# LightSensor1.net
KiCad netlist of a schematic drawn in EAGLE
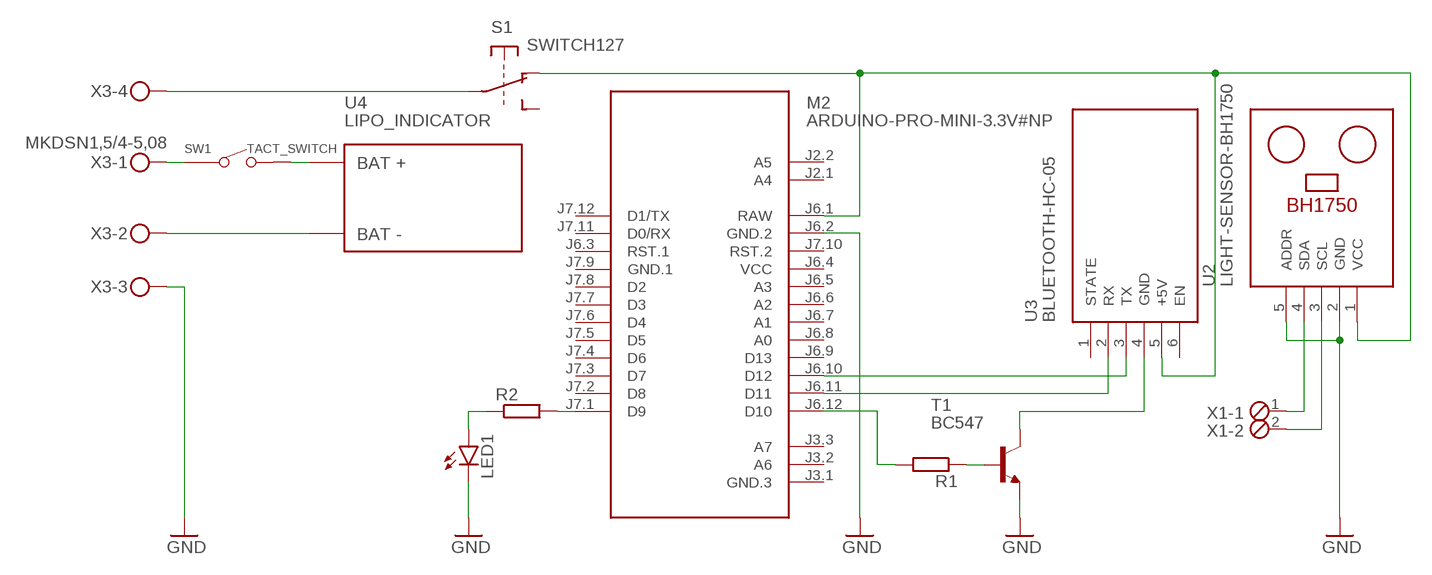
[diagram p0: schematic, sheet 1]

(export (version "E")
  (design (tool "Eeschema 10.0.6"))
  (components
    (comp (ref "LED1")
      (value "LED3MM")
      (footprint "eagle-import:LED3MM")
      (libsource (lib "eagle-import") (part "LED3MM"))
    )
    (comp (ref "M2")
      (value "ARDUINO-PRO-MINI-3.3V#NP")
      (footprint "eagle-import:ARDUINO-PRO-MINI#NP")
      (libsource (lib "eagle-import") (part "ARDUINO-PRO-MINI-#NP3.3V"))
    )
    (comp (ref "R1")
      (value "R-EU_0207/10")
      (footprint "eagle-import:0207_10")
      (libsource (lib "eagle-import") (part "R-EU_0207/10"))
    )
    (comp (ref "R2")
      (value "R-EU_0207/10")
      (footprint "eagle-import:0207_10")
      (libsource (lib "eagle-import") (part "R-EU_0207/10"))
    )
    (comp (ref "S1")
      (value "SWITCH127")
      (footprint "eagle-import:SWITCH127")
      (libsource (lib "eagle-import") (part "SWITCH127"))
    )
    (comp (ref "SW1")
      (value "TACT_SWITCH")
      (footprint "eagle-import:SW2-5.0-6.0X3.0X4.3MM")
      (libsource (lib "eagle-import") (part "TACT_SWITCH"))
    )
    (comp (ref "T1")
      (value "BC547")
      (footprint "eagle-import:TO92")
      (libsource (lib "eagle-import") (part "BC547"))
    )
    (comp (ref "U2")
      (value "LIGHT-SENSOR-BH1750")
      (footprint "eagle-import:LIGHT-SENSOR-BH1750")
      (libsource (lib "eagle-import") (part "LIGHT-SENSOR-BH1750"))
    )
    (comp (ref "U3")
      (value "BLUETOOTH-HC-05")
      (footprint "eagle-import:WIRELESS-BLUETOOTH-HC-05")
      (libsource (lib "eagle-import") (part "WIRELESS-BLUETOOTH-HC-05"))
    )
    (comp (ref "U4")
      (value "LIPO_INDICATOR")
      (footprint "eagle-import:INDICATROR_NR1")
      (libsource (lib "eagle-import") (part "LIPO_INDICATOR"))
    )
    (comp (ref "X1")
      (value "MPT2")
      (footprint "eagle-import:2POL254")
      (libsource (lib "eagle-import") (part "MPT2"))
    )
    (comp (ref "X3")
      (value "MKDSN1,5/4-5,08")
      (footprint "eagle-import:MKDSN1,5_4-5,08")
      (libsource (lib "eagle-import") (part "MKDSN1,5/4-5,08"))
    )
  )
  (nets
    (net (code "1") (name "/GND.1") (class "Default")
      (node (ref "M2") (pin "J7.9") (pinfunction "GND.1_J7.9") (pintype "power_in"))
    )
    (net (code "2") (name "/VCC") (class "Default")
      (node (ref "M2") (pin "J6.4") (pinfunction "VCC_J6.4") (pintype "power_in"))
    )
    (net (code "3") (name "GND") (class "Default")
      (node (ref "LED1") (pin "K") (pinfunction "C_K") (pintype "passive"))
      (node (ref "M2") (pin "J6.2") (pinfunction "GND.2_J6.2") (pintype "power_in"))
      (node (ref "T1") (pin "1") (pinfunction "E_1") (pintype "passive"))
      (node (ref "U2") (pin "2") (pinfunction "GND_2") (pintype "power_in"))
      (node (ref "U2") (pin "5") (pinfunction "ADDR_5") (pintype "bidirectional"))
      (node (ref "X3") (pin "3") (pinfunction "KL_3") (pintype "passive"))
    )
    (net (code "4") (name "Net-(LED1-PadA)") (class "Default")
      (node (ref "LED1") (pin "A") (pinfunction "A_A") (pintype "passive"))
      (node (ref "R2") (pin "1") (pinfunction "1_1") (pintype "passive"))
    )
    (net (code "5") (name "Net-(M2-D9)") (class "Default")
      (node (ref "M2") (pin "J7.1") (pinfunction "D9_J7.1") (pintype "bidirectional"))
      (node (ref "R2") (pin "2") (pinfunction "2_2") (pintype "passive"))
    )
    (net (code "6") (name "Net-(M2-D10)") (class "Default")
      (node (ref "M2") (pin "J6.12") (pinfunction "D10_J6.12") (pintype "bidirectional"))
      (node (ref "R1") (pin "2") (pinfunction "2_2") (pintype "passive"))
    )
    (net (code "7") (name "Net-(M2-D11)") (class "Default")
      (node (ref "M2") (pin "J6.11") (pinfunction "D11_J6.11") (pintype "bidirectional"))
      (node (ref "U3") (pin "2") (pinfunction "RX_2") (pintype "bidirectional"))
    )
    (net (code "8") (name "Net-(M2-D12)") (class "Default")
      (node (ref "M2") (pin "J6.10") (pinfunction "D12_J6.10") (pintype "bidirectional"))
      (node (ref "U3") (pin "3") (pinfunction "TX_3") (pintype "bidirectional"))
    )
    (net (code "9") (name "Net-(M2-RAW)") (class "Default")
      (node (ref "M2") (pin "J6.1") (pinfunction "RAW_J6.1") (pintype "power_in"))
      (node (ref "S1") (pin "P$3") (pinfunction "3_P$3") (pintype "passive"))
      (node (ref "U2") (pin "1") (pinfunction "VCC_1") (pintype "power_in"))
      (node (ref "U3") (pin "5") (pinfunction "+5V_5") (pintype "power_in"))
    )
    (net (code "10") (name "Net-(S1-2)") (class "Default")
      (node (ref "S1") (pin "P$2") (pinfunction "2_P$2") (pintype "passive"))
      (node (ref "X3") (pin "4") (pinfunction "KL_4") (pintype "passive"))
    )
    (net (code "11") (name "Net-(T1-B)") (class "Default")
      (node (ref "R1") (pin "1") (pinfunction "1_1") (pintype "passive"))
      (node (ref "T1") (pin "2") (pinfunction "B_2") (pintype "passive"))
    )
    (net (code "12") (name "Net-(T1-C)") (class "Default")
      (node (ref "T1") (pin "3") (pinfunction "C_3") (pintype "passive"))
      (node (ref "U3") (pin "4") (pinfunction "GND_4") (pintype "power_in"))
    )
    (net (code "13") (name "Net-(U2-SCL)") (class "Default")
      (node (ref "U2") (pin "3") (pinfunction "SCL_3") (pintype "bidirectional"))
      (node (ref "X1") (pin "2") (pinfunction "1_2") (pintype "passive"))
    )
    (net (code "14") (name "Net-(U2-SDA)") (class "Default")
      (node (ref "U2") (pin "4") (pinfunction "SDA_4") (pintype "bidirectional"))
      (node (ref "X1") (pin "1") (pinfunction "1_1") (pintype "passive"))
    )
    (net (code "15") (name "Net-(U4-P$1)") (class "Default")
      (node (ref "SW1") (pin "2") (pinfunction "2_2") (pintype "bidirectional"))
      (node (ref "U4") (pin "+BAT") (pinfunction "P$1_+BAT") (pintype "input"))
    )
    (net (code "16") (name "Net-(U4-P$2)") (class "Default")
      (node (ref "U4") (pin "-BAT") (pinfunction "P$2_-BAT") (pintype "input"))
      (node (ref "X3") (pin "2") (pinfunction "KL_2") (pintype "passive"))
    )
    (net (code "17") (name "Net-(X3A-KL)") (class "Default")
      (node (ref "SW1") (pin "1") (pinfunction "1_1") (pintype "bidirectional"))
      (node (ref "X3") (pin "1") (pinfunction "KL_1") (pintype "passive"))
    )
    (net (code "18") (name "unconnected-(M2-A0-PadJ6.8)") (class "Default")
      (node (ref "M2") (pin "J6.8") (pinfunction "A0_J6.8") (pintype "bidirectional"))
    )
    (net (code "19") (name "unconnected-(M2-A1-PadJ6.7)") (class "Default")
      (node (ref "M2") (pin "J6.7") (pinfunction "A1_J6.7") (pintype "bidirectional"))
    )
    (net (code "20") (name "unconnected-(M2-A2-PadJ6.6)") (class "Default")
      (node (ref "M2") (pin "J6.6") (pinfunction "A2_J6.6") (pintype "bidirectional"))
    )
    (net (code "21") (name "unconnected-(M2-A3-PadJ6.5)") (class "Default")
      (node (ref "M2") (pin "J6.5") (pinfunction "A3_J6.5") (pintype "bidirectional"))
    )
    (net (code "22") (name "unconnected-(M2-A4-PadJ2.1)") (class "Default")
      (node (ref "M2") (pin "J2.1") (pinfunction "A4_J2.1") (pintype "bidirectional"))
    )
    (net (code "23") (name "unconnected-(M2-A5-PadJ2.2)") (class "Default")
      (node (ref "M2") (pin "J2.2") (pinfunction "A5_J2.2") (pintype "bidirectional"))
    )
    (net (code "24") (name "unconnected-(M2-A6-PadJ3.2)") (class "Default")
      (node (ref "M2") (pin "J3.2") (pinfunction "A6_J3.2") (pintype "bidirectional"))
    )
    (net (code "25") (name "unconnected-(M2-A7-PadJ3.3)") (class "Default")
      (node (ref "M2") (pin "J3.3") (pinfunction "A7_J3.3") (pintype "bidirectional"))
    )
    (net (code "26") (name "unconnected-(M2-D0{slash}RX-PadJ7.11)") (class "Default")
      (node (ref "M2") (pin "J7.11") (pinfunction "D0/RX_J7.11") (pintype "bidirectional"))
    )
    (net (code "27") (name "unconnected-(M2-D1{slash}TX-PadJ7.12)") (class "Default")
      (node (ref "M2") (pin "J7.12") (pinfunction "D1/TX_J7.12") (pintype "bidirectional"))
    )
    (net (code "28") (name "unconnected-(M2-D2-PadJ7.8)") (class "Default")
      (node (ref "M2") (pin "J7.8") (pinfunction "D2_J7.8") (pintype "bidirectional"))
    )
    (net (code "29") (name "unconnected-(M2-D3-PadJ7.7)") (class "Default")
      (node (ref "M2") (pin "J7.7") (pinfunction "D3_J7.7") (pintype "bidirectional"))
    )
    (net (code "30") (name "unconnected-(M2-D4-PadJ7.6)") (class "Default")
      (node (ref "M2") (pin "J7.6") (pinfunction "D4_J7.6") (pintype "bidirectional"))
    )
    (net (code "31") (name "unconnected-(M2-D5-PadJ7.5)") (class "Default")
      (node (ref "M2") (pin "J7.5") (pinfunction "D5_J7.5") (pintype "bidirectional"))
    )
    (net (code "32") (name "unconnected-(M2-D6-PadJ7.4)") (class "Default")
      (node (ref "M2") (pin "J7.4") (pinfunction "D6_J7.4") (pintype "bidirectional"))
    )
    (net (code "33") (name "unconnected-(M2-D7-PadJ7.3)") (class "Default")
      (node (ref "M2") (pin "J7.3") (pinfunction "D7_J7.3") (pintype "bidirectional"))
    )
    (net (code "34") (name "unconnected-(M2-D8-PadJ7.2)") (class "Default")
      (node (ref "M2") (pin "J7.2") (pinfunction "D8_J7.2") (pintype "bidirectional"))
    )
    (net (code "35") (name "unconnected-(M2-D13-PadJ6.9)") (class "Default")
      (node (ref "M2") (pin "J6.9") (pinfunction "D13_J6.9") (pintype "bidirectional"))
    )
    (net (code "36") (name "unconnected-(M2-GND.3-PadJ3.1)") (class "Default")
      (node (ref "M2") (pin "J3.1") (pinfunction "GND.3_J3.1") (pintype "bidirectional"))
    )
    (net (code "37") (name "unconnected-(M2-RST.1-PadJ6.3)") (class "Default")
      (node (ref "M2") (pin "J6.3") (pinfunction "RST.1_J6.3") (pintype "bidirectional"))
    )
    (net (code "38") (name "unconnected-(M2-RST.2-PadJ7.10)") (class "Default")
      (node (ref "M2") (pin "J7.10") (pinfunction "RST.2_J7.10") (pintype "bidirectional"))
    )
    (net (code "39") (name "unconnected-(S1-1-PadP$1)") (class "Default")
      (node (ref "S1") (pin "P$1") (pinfunction "1_P$1") (pintype "passive"))
    )
    (net (code "40") (name "unconnected-(U3-EN-Pad6)") (class "Default")
      (node (ref "U3") (pin "6") (pinfunction "EN_6") (pintype "bidirectional"))
    )
    (net (code "41") (name "unconnected-(U3-STATE-Pad1)") (class "Default")
      (node (ref "U3") (pin "1") (pinfunction "STATE_1") (pintype "bidirectional"))
    )
  )
)
